# power.net
KiCad netlist of a schematic drawn in Altium Designer
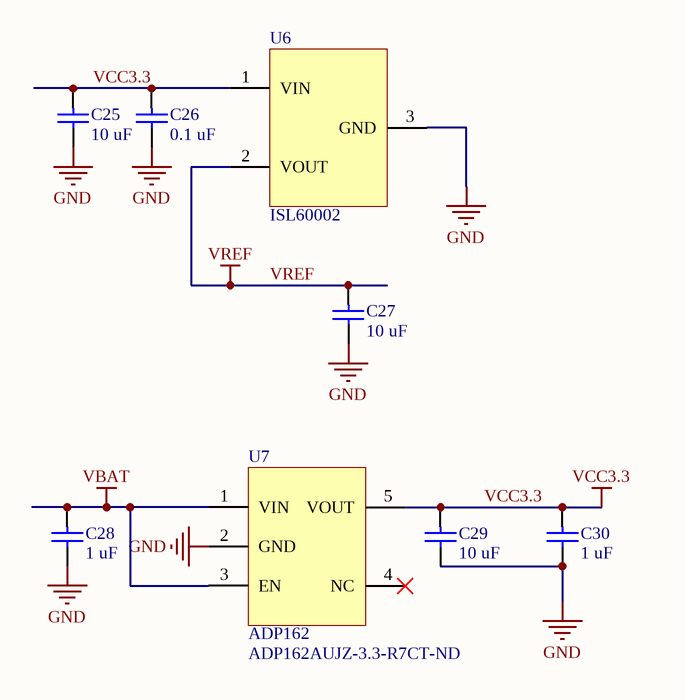
[diagram p0: power.SchDoc]

(export (version "E")
  (design (tool "Eeschema 10.0.6"))
  (components
    (comp (ref "C25")
      (value "10 uF")
      (footprint "0603")
      (description "Ceramic capacitor, 10 uF, 0603 package")
      (fields (field (name "TOLERANCE") "20%") (field (name "Comment") "Ceramic capacitor"))
      (libsource (lib "rlc") (part "C_10u_0603_ceramic"))
    )
    (comp (ref "C26")
      (value "0.1 uF")
      (footprint "0402")
      (description "Ceramic capacitor, 0.1u, 0402 package")
      (fields (field (name "TOLERANCE") "10%") (field (name "Comment") "Ceramic capacitor"))
      (libsource (lib "rlc") (part "C_0.1u_0402_ceramic"))
    )
    (comp (ref "C27")
      (value "10 uF")
      (footprint "0603")
      (description "Ceramic capacitor, 10 uF, 0603 package")
      (fields (field (name "TOLERANCE") "20%") (field (name "Comment") "Ceramic capacitor"))
      (libsource (lib "rlc") (part "C_10u_0603_ceramic"))
    )
    (comp (ref "C28")
      (value "1 uF")
      (footprint "0402")
      (description "Ceramic capacitor, 1 uF, 0402 package")
      (fields (field (name "TOLERANCE") "10%") (field (name "Comment") "Ceramic capacitor"))
      (libsource (lib "rlc") (part "C_1u_0402_ceramic"))
    )
    (comp (ref "C29")
      (value "10 uF")
      (footprint "0603")
      (description "Ceramic capacitor, 10 uF, 0603 package")
      (fields (field (name "TOLERANCE") "20%") (field (name "Comment") "Ceramic capacitor"))
      (libsource (lib "rlc") (part "C_10u_0603_ceramic"))
    )
    (comp (ref "C30")
      (value "1 uF")
      (footprint "0402")
      (description "Ceramic capacitor, 1 uF, 0402 package")
      (fields (field (name "TOLERANCE") "10%") (field (name "Comment") "Ceramic capacitor"))
      (libsource (lib "rlc") (part "C_1u_0402_ceramic"))
    )
    (comp (ref "U6")
      (value "ISL60002")
      (footprint "SOT23-3N")
      (description "IC VREF SERIES PREC SOT-23-3")
      (libsource (lib "opo") (part "ISL60002"))
    )
    (comp (ref "U7")
      (value "ADP162")
      (footprint "TSOT23-5")
      (description "Ultralow Quiescent Current,  150 mA, CMOS Linear Regulators")
      (fields (field (name "SUPPLIER PART NUMBER 1") "ADP162AUJZ-3.3-R7CT-ND"))
      (libsource (lib "opo") (part "ADP162"))
    )
  )
  (nets
    (net (code "1") (name "GND") (class "Default")
      (node (ref "C25") (pin "2") (pintype "passive"))
      (node (ref "C26") (pin "2") (pintype "passive"))
      (node (ref "C27") (pin "2") (pintype "passive"))
      (node (ref "C28") (pin "2") (pintype "passive"))
      (node (ref "C29") (pin "2") (pintype "passive"))
      (node (ref "C30") (pin "2") (pintype "passive"))
      (node (ref "U6") (pin "3") (pinfunction "GND_3") (pintype "passive"))
      (node (ref "U7") (pin "2") (pinfunction "GND_2") (pintype "passive"))
    )
    (net (code "2") (name "VBAT") (class "Default")
      (node (ref "C28") (pin "1") (pintype "passive"))
      (node (ref "U7") (pin "1") (pinfunction "VIN_1") (pintype "passive"))
      (node (ref "U7") (pin "3") (pinfunction "EN_3") (pintype "passive"))
    )
    (net (code "3") (name "VCC3.3") (class "Default")
      (node (ref "C25") (pin "1") (pintype "passive"))
      (node (ref "C26") (pin "1") (pintype "passive"))
      (node (ref "C29") (pin "1") (pintype "passive"))
      (node (ref "C30") (pin "1") (pintype "passive"))
      (node (ref "U6") (pin "1") (pinfunction "VIN_1") (pintype "passive"))
      (node (ref "U7") (pin "5") (pinfunction "VOUT_5") (pintype "passive"))
    )
    (net (code "4") (name "VREF") (class "Default")
      (node (ref "C27") (pin "1") (pintype "passive"))
      (node (ref "U6") (pin "2") (pinfunction "VOUT_2") (pintype "passive"))
    )
    (net (code "5") (name "unconnected-(U7-NC-Pad4)") (class "Default")
      (node (ref "U7") (pin "4") (pinfunction "NC_4") (pintype "passive+no_connect"))
    )
  )
)
